# PowerBoard.net
KiCad netlist of a schematic drawn in Altium Designer
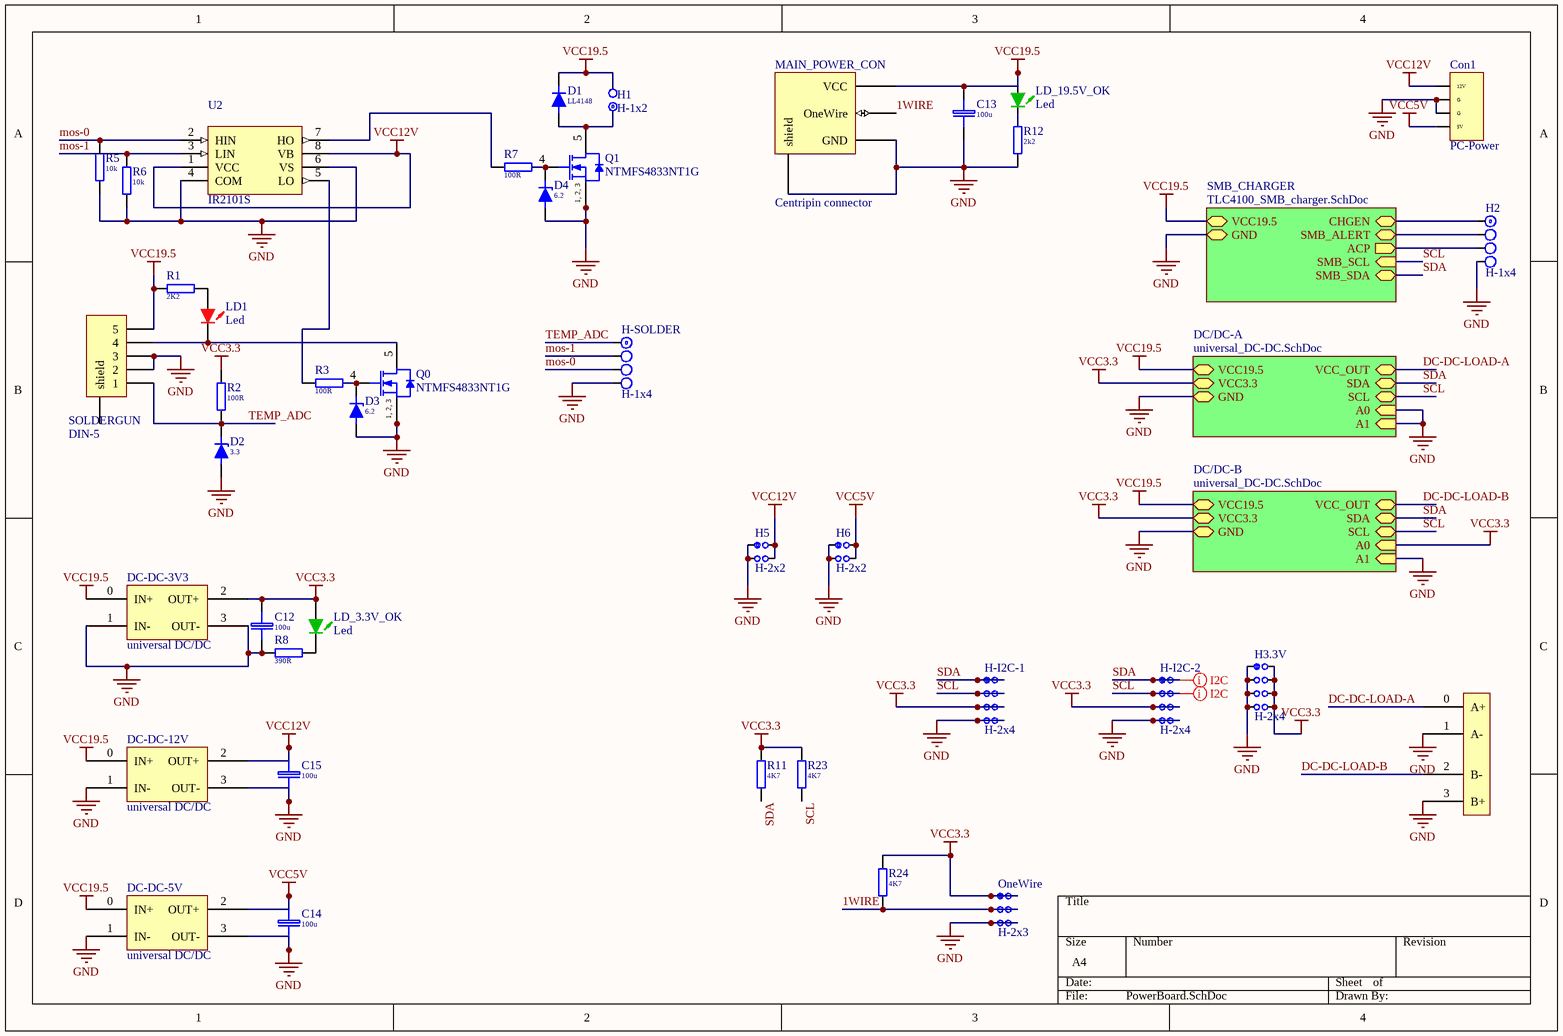
[diagram p0: PowerBoard.SchDoc]

(export (version "E")
  (design (tool "Eeschema 10.0.6"))
  (components
    (comp (ref "C12")
      (value "100u")
      (footprint "EL SMD Case G D10x10.3 h10.2(1010)")
      (description "EL 35V SMD Case G D10x10.3h10.5")
      (libsource (lib "SMD-RCL") (part "EL 100u/35V"))
    )
    (comp (ref "C13")
      (value "100u")
      (footprint "EL SMD Case G D10x10.3 h10.2(1010)")
      (description "EL 35V SMD Case G D10x10.3h10.5")
      (libsource (lib "SMD-RCL") (part "EL 100u/35V"))
    )
    (comp (ref "C14")
      (value "100u")
      (footprint "EL SMD Case G D10x10.3 h10.2(1010)")
      (description "EL 35V SMD Case G D10x10.3h10.5")
      (libsource (lib "SMD-RCL") (part "EL 100u/35V"))
    )
    (comp (ref "C15")
      (value "100u")
      (footprint "EL SMD Case G D10x10.3 h10.2(1010)")
      (description "EL 35V SMD Case G D10x10.3h10.5")
      (libsource (lib "SMD-RCL") (part "EL 100u/35V"))
    )
    (comp (ref "Con1")
      (value "PC-Power")
      (footprint "PC-Power 4x5.08")
      (description "PC-Power 4x5.08")
      (libsource (lib "Connektor") (part "PC-Power 4x5.08"))
    )
    (comp (ref "CON_DC_DC")
      (value "Speaker terminal 4P")
      (footprint "Speaker termina 4x DPS")
      (libsource (lib "Altium_okruh_miscLib") (part "Speaker terminal 4P"))
    )
    (comp (ref "D1")
      (value "LL4148")
      (footprint "Micro-Melf")
      (description "SMD Micro-Melf 75V 0.3A")
      (libsource (lib "Diodes") (part "MCL4148"))
    )
    (comp (ref "D2")
      (value "3.3")
      (footprint "SOD323")
      (description "3.3V 0.2W")
      (libsource (lib "Diodes") (part "ZD3.3"))
    )
    (comp (ref "D3")
      (value "6.2")
      (footprint "SOD323")
      (description "6.2V 0.2W")
      (libsource (lib "Diodes") (part "ZD6.2"))
    )
    (comp (ref "D4")
      (value "6.2")
      (footprint "SOD323")
      (description "6.2V 0.2W")
      (libsource (lib "Diodes") (part "ZD6.2"))
    )
    (comp (ref "DC-DC-3V3")
      (value "universal DC/DC")
      (footprint "MP1584EN dc/dc 3A vertical")
      (libsource (lib "Altium_okruh_miscLib") (part "universal DC/DC"))
    )
    (comp (ref "DC-DC-5V")
      (value "universal DC/DC")
      (footprint "MP1584EN dc/dc 3A vertical")
      (libsource (lib "Altium_okruh_miscLib") (part "universal DC/DC"))
    )
    (comp (ref "DC-DC-12V")
      (value "universal DC/DC")
      (footprint "MP1584EN dc/dc 3A vertical")
      (libsource (lib "Altium_okruh_miscLib") (part "universal DC/DC"))
    )
    (comp (ref "H-I2C-1") (value "H-2x4") (footprint "J2x4") (libsource (lib "Connektor") (part "H-2x4")))
    (comp (ref "H-I2C-2") (value "H-2x4") (footprint "J2x4") (libsource (lib "Connektor") (part "H-2x4")))
    (comp (ref "H-SOLDER") (value "H-1x4") (footprint "J1x4") (libsource (lib "Connektor") (part "H-1x4")))
    (comp (ref "H1") (value "H-1x2") (footprint "J1x2") (libsource (lib "Connektor") (part "H-1x2")))
    (comp (ref "H2") (value "H-1x4") (footprint "J1x4") (libsource (lib "Connektor") (part "H-1x4")))
    (comp (ref "H3.3V") (value "H-2x4") (footprint "J2x4") (libsource (lib "Connektor") (part "H-2x4")))
    (comp (ref "H5") (value "H-2x2") (footprint "J2x2") (libsource (lib "Connektor") (part "H-2x2")))
    (comp (ref "H6") (value "H-2x2") (footprint "J2x2") (libsource (lib "Connektor") (part "H-2x2")))
    (comp (ref "LD1")
      (value "Led")
      (footprint "Led 0805-Red")
      (description "Red  627nm 12mcd")
      (libsource (lib "Ind LED-LCD") (part "Led 0805 KP-2012EC"))
    )
    (comp (ref "LD_3.3V_OK")
      (value "Led")
      (footprint "Led 0805-Green")
      (description "Green 565nm 15mcd")
      (libsource (lib "Ind LED-LCD") (part "Led 0805 KP-2012SGC"))
    )
    (comp (ref "LD_19.5V_OK")
      (value "Led")
      (footprint "Led 0805-Green")
      (description "Green 565nm 15mcd")
      (libsource (lib "Ind LED-LCD") (part "Led 0805 KP-2012SGC"))
    )
    (comp (ref "MAIN_POWER_CON")
      (value "Centripin connector")
      (footprint "Dell_centripin")
      (libsource (lib "Altium_okruh_miscLib") (part "Centripin connector"))
    )
    (comp (ref "OneWire") (value "H-2x3") (footprint "J2x3") (libsource (lib "Connektor") (part "H-2x3")))
    (comp (ref "Q0")
      (value "NTMFS4833NT1G")
      (footprint "ONSC-DFN-5-488AA_V")
      (description "Power MOSFET, 30 V, 191 A, Single N-Channel, 5-Pin DFN, Pb-Free, Tape and Reel")
      (fields (field (name "MANUFACTURER") "On Semiconductor"))
      (libsource (lib "ON Semi MOSFETs") (part "NTMFS4833NT1G"))
    )
    (comp (ref "Q1")
      (value "NTMFS4833NT1G")
      (footprint "ONSC-DFN-5-488AA_V")
      (description "Power MOSFET, 30 V, 191 A, Single N-Channel, 5-Pin DFN, Pb-Free, Tape and Reel")
      (fields (field (name "MANUFACTURER") "On Semiconductor"))
      (libsource (lib "ON Semi MOSFETs") (part "NTMFS4833NT1G"))
    )
    (comp (ref "R1")
      (value "2K2")
      (footprint "R0805")
      (description "SMD 0805 0.1W 5% 150V")
      (libsource (lib "SMD-RCL") (part "R-0805"))
    )
    (comp (ref "R2")
      (value "100R")
      (footprint "R0805")
      (description "SMD 0805 0.1W 5% 150V")
      (libsource (lib "SMD-RCL") (part "R-0805"))
    )
    (comp (ref "R3")
      (value "100R")
      (footprint "R0805")
      (description "SMD 0805 0.1W 5% 150V")
      (libsource (lib "SMD-RCL") (part "R-0805"))
    )
    (comp (ref "R5")
      (value "10k")
      (footprint "R0805")
      (description "SMD 0805 0.1W 5% 150V")
      (libsource (lib "SMD-RCL") (part "R-0805"))
    )
    (comp (ref "R6")
      (value "10k")
      (footprint "R0805")
      (description "SMD 0805 0.1W 5% 150V")
      (libsource (lib "SMD-RCL") (part "R-0805"))
    )
    (comp (ref "R7")
      (value "100R")
      (footprint "R0805")
      (description "SMD 0805 0.1W 5% 150V")
      (libsource (lib "SMD-RCL") (part "R-0805"))
    )
    (comp (ref "R8")
      (value "390R")
      (footprint "R0805")
      (description "SMD 0805 0.1W 5% 150V")
      (libsource (lib "SMD-RCL") (part "R-0805"))
    )
    (comp (ref "R11")
      (value "4K7")
      (footprint "R0805")
      (description "SMD 0805 0.1W 5% 150V")
      (libsource (lib "SMD-RCL") (part "R-0805"))
    )
    (comp (ref "R12")
      (value "2k2")
      (footprint "R0805")
      (description "SMD 0805 0.1W 5% 150V")
      (libsource (lib "SMD-RCL") (part "R-0805"))
    )
    (comp (ref "R23")
      (value "4K7")
      (footprint "R0805")
      (description "SMD 0805 0.1W 5% 150V")
      (libsource (lib "SMD-RCL") (part "R-0805"))
    )
    (comp (ref "R24")
      (value "4K7")
      (footprint "R0805")
      (description "SMD 0805 0.1W 5% 150V")
      (libsource (lib "SMD-RCL") (part "R-0805"))
    )
    (comp (ref "SOLDERGUN")
      (value "DIN-5")
      (footprint "DIN-5")
      (libsource (lib "Altium_okruh_miscLib") (part "DIN-5"))
    )
    (comp (ref "U2")
      (value "IR2101S")
      (footprint "SO-8_L")
      (description "High and Low Side Driver")
      (fields (field (name "PUBLISHER") "Altium Limited"))
      (libsource (lib "IR Interface Bridge Driver") (part "IR2101S"))
    )
  )
  (nets
    (net (code "1") (name "/1WIRE") (class "Default")
      (node (ref "MAIN_POWER_CON") (pin "2") (pinfunction "OneWire_2") (pintype "bidirectional"))
      (node (ref "OneWire") (pin "3") (pinfunction "3_3") (pintype "passive"))
      (node (ref "OneWire") (pin "4") (pinfunction "4_4") (pintype "passive"))
      (node (ref "R24") (pin "1") (pinfunction "1_1") (pintype "passive"))
    )
    (net (code "2") (name "/ACP") (class "Default")
      (node (ref "H2") (pin "3") (pinfunction "3_3") (pintype "passive"))
    )
    (net (code "3") (name "/CHGEN") (class "Default")
      (node (ref "H2") (pin "1") (pinfunction "1_1") (pintype "passive"))
    )
    (net (code "4") (name "/DC-DC-LOAD-A") (class "Default")
      (node (ref "CON_DC_DC") (pin "0") (pinfunction "A+_0") (pintype "passive"))
    )
    (net (code "5") (name "/DC-DC-LOAD-B") (class "Default")
      (node (ref "CON_DC_DC") (pin "2") (pinfunction "B-_2") (pintype "passive"))
    )
    (net (code "6") (name "/SCL") (class "Default")
      (node (ref "H-I2C-1") (pin "3") (pinfunction "3_3") (pintype "passive"))
      (node (ref "H-I2C-1") (pin "4") (pinfunction "4_4") (pintype "passive"))
      (node (ref "H-I2C-2") (pin "3") (pinfunction "3_3") (pintype "passive"))
      (node (ref "H-I2C-2") (pin "4") (pinfunction "4_4") (pintype "passive"))
      (node (ref "R23") (pin "1") (pinfunction "1_1") (pintype "passive"))
    )
    (net (code "7") (name "/SDA") (class "Default")
      (node (ref "H-I2C-1") (pin "1") (pinfunction "1_1") (pintype "passive"))
      (node (ref "H-I2C-1") (pin "2") (pinfunction "2_2") (pintype "passive"))
      (node (ref "H-I2C-2") (pin "1") (pinfunction "1_1") (pintype "passive"))
      (node (ref "H-I2C-2") (pin "2") (pinfunction "2_2") (pintype "passive"))
      (node (ref "R11") (pin "1") (pinfunction "1_1") (pintype "passive"))
    )
    (net (code "8") (name "/SMB_ALERT") (class "Default")
      (node (ref "H2") (pin "2") (pinfunction "2_2") (pintype "passive"))
    )
    (net (code "9") (name "/TEMP_ADC") (class "Default")
      (node (ref "D2") (pin "2") (pinfunction "C_2") (pintype "passive"))
      (node (ref "H-SOLDER") (pin "1") (pinfunction "1_1") (pintype "passive"))
      (node (ref "R2") (pin "1") (pinfunction "1_1") (pintype "passive"))
      (node (ref "SOLDERGUN") (pin "1") (pinfunction "1_1") (pintype "passive"))
    )
    (net (code "10") (name "/mos-0") (class "Default")
      (node (ref "H-SOLDER") (pin "3") (pinfunction "3_3") (pintype "passive"))
      (node (ref "R5") (pin "2") (pinfunction "2_2") (pintype "passive"))
      (node (ref "U2") (pin "2") (pinfunction "HIN_2") (pintype "input"))
    )
    (net (code "11") (name "/mos-1") (class "Default")
      (node (ref "H-SOLDER") (pin "2") (pinfunction "2_2") (pintype "passive"))
      (node (ref "R6") (pin "2") (pinfunction "2_2") (pintype "passive"))
      (node (ref "U2") (pin "3") (pinfunction "LIN_3") (pintype "input"))
    )
    (net (code "12") (name "GND") (class "Default")
      (node (ref "C12") (pin "2") (pinfunction "-_2") (pintype "passive"))
      (node (ref "C13") (pin "2") (pinfunction "-_2") (pintype "passive"))
      (node (ref "C14") (pin "2") (pinfunction "-_2") (pintype "passive"))
      (node (ref "C15") (pin "2") (pinfunction "-_2") (pintype "passive"))
      (node (ref "CON_DC_DC") (pin "1") (pinfunction "A-_1") (pintype "passive"))
      (node (ref "CON_DC_DC") (pin "3") (pinfunction "B+_3") (pintype "passive"))
      (node (ref "Con1") (pin "2") (pinfunction "G_2") (pintype "passive"))
      (node (ref "Con1") (pin "3") (pinfunction "G_3") (pintype "passive"))
      (node (ref "D2") (pin "1") (pinfunction "A_1") (pintype "passive"))
      (node (ref "D3") (pin "1") (pinfunction "A_1") (pintype "passive"))
      (node (ref "D4") (pin "1") (pinfunction "A_1") (pintype "passive"))
      (node (ref "DC-DC-12V") (pin "1") (pinfunction "IN-_1") (pintype "power_in"))
      (node (ref "DC-DC-12V") (pin "3") (pinfunction "OUT-_3") (pintype "power_in"))
      (node (ref "DC-DC-3V3") (pin "1") (pinfunction "IN-_1") (pintype "power_in"))
      (node (ref "DC-DC-3V3") (pin "3") (pinfunction "OUT-_3") (pintype "power_in"))
      (node (ref "DC-DC-5V") (pin "1") (pinfunction "IN-_1") (pintype "power_in"))
      (node (ref "DC-DC-5V") (pin "3") (pinfunction "OUT-_3") (pintype "power_in"))
      (node (ref "H-I2C-1") (pin "7") (pinfunction "7_7") (pintype "passive"))
      (node (ref "H-I2C-1") (pin "8") (pinfunction "8_8") (pintype "passive"))
      (node (ref "H-I2C-2") (pin "7") (pinfunction "7_7") (pintype "passive"))
      (node (ref "H-I2C-2") (pin "8") (pinfunction "8_8") (pintype "passive"))
      (node (ref "H-SOLDER") (pin "4") (pinfunction "4_4") (pintype "passive"))
      (node (ref "H2") (pin "4") (pinfunction "4_4") (pintype "passive"))
      (node (ref "H3.3V") (pin "1") (pinfunction "1_1") (pintype "passive"))
      (node (ref "H3.3V") (pin "3") (pinfunction "3_3") (pintype "passive"))
      (node (ref "H3.3V") (pin "5") (pinfunction "5_5") (pintype "passive"))
      (node (ref "H3.3V") (pin "7") (pinfunction "7_7") (pintype "passive"))
      (node (ref "H5") (pin "1") (pinfunction "1_1") (pintype "passive"))
      (node (ref "H5") (pin "3") (pinfunction "3_3") (pintype "passive"))
      (node (ref "H6") (pin "1") (pinfunction "1_1") (pintype "passive"))
      (node (ref "H6") (pin "3") (pinfunction "3_3") (pintype "passive"))
      (node (ref "MAIN_POWER_CON") (pin "0") (pinfunction "shield_0") (pintype "passive"))
      (node (ref "MAIN_POWER_CON") (pin "1") (pinfunction "GND_1") (pintype "passive"))
      (node (ref "OneWire") (pin "5") (pinfunction "5_5") (pintype "passive"))
      (node (ref "OneWire") (pin "6") (pinfunction "6_6") (pintype "passive"))
      (node (ref "Q0") (pin "1") (pinfunction "S_1") (pintype "passive"))
      (node (ref "Q0") (pin "2") (pinfunction "S_2") (pintype "passive"))
      (node (ref "Q0") (pin "3") (pinfunction "S_3") (pintype "passive"))
      (node (ref "Q1") (pin "1") (pinfunction "S_1") (pintype "passive"))
      (node (ref "Q1") (pin "2") (pinfunction "S_2") (pintype "passive"))
      (node (ref "Q1") (pin "3") (pinfunction "S_3") (pintype "passive"))
      (node (ref "R12") (pin "2") (pinfunction "2_2") (pintype "passive"))
      (node (ref "R5") (pin "1") (pinfunction "1_1") (pintype "passive"))
      (node (ref "R6") (pin "1") (pinfunction "1_1") (pintype "passive"))
      (node (ref "R8") (pin "2") (pinfunction "2_2") (pintype "passive"))
      (node (ref "SOLDERGUN") (pin "2") (pinfunction "2_2") (pintype "passive"))
      (node (ref "SOLDERGUN") (pin "3") (pinfunction "3_3") (pintype "passive"))
      (node (ref "U2") (pin "4") (pinfunction "COM_4") (pintype "power_in"))
      (node (ref "U2") (pin "6") (pinfunction "VS_6") (pintype "power_in"))
    )
    (net (code "13") (name "Net-(D1-A)") (class "Default")
      (node (ref "D1") (pin "1") (pinfunction "A_1") (pintype "passive"))
      (node (ref "H1") (pin "1") (pinfunction "1_1") (pintype "passive"))
      (node (ref "Q1") (pin "5") (pinfunction "D_5") (pintype "passive"))
    )
    (net (code "14") (name "Net-(D3-C)") (class "Default")
      (node (ref "D3") (pin "2") (pinfunction "C_2") (pintype "passive"))
      (node (ref "Q0") (pin "4") (pinfunction "G_4") (pintype "passive"))
      (node (ref "R3") (pin "1") (pinfunction "1_1") (pintype "passive"))
    )
    (net (code "15") (name "Net-(D4-C)") (class "Default")
      (node (ref "D4") (pin "2") (pinfunction "C_2") (pintype "passive"))
      (node (ref "Q1") (pin "4") (pinfunction "G_4") (pintype "passive"))
      (node (ref "R7") (pin "1") (pinfunction "1_1") (pintype "passive"))
    )
    (net (code "16") (name "Net-(LD1-A)") (class "Default")
      (node (ref "LD1") (pin "1") (pinfunction "A_1") (pintype "passive"))
      (node (ref "R1") (pin "1") (pinfunction "1_1") (pintype "passive"))
    )
    (net (code "17") (name "Net-(LD1-K)") (class "Default")
      (node (ref "LD1") (pin "2") (pinfunction "K_2") (pintype "passive"))
      (node (ref "Q0") (pin "5") (pinfunction "D_5") (pintype "passive"))
      (node (ref "SOLDERGUN") (pin "4") (pinfunction "4_4") (pintype "passive"))
    )
    (net (code "18") (name "Net-(LD_3.3V_OK-K)") (class "Default")
      (node (ref "LD_3.3V_OK") (pin "2") (pinfunction "K_2") (pintype "passive"))
      (node (ref "R8") (pin "1") (pinfunction "1_1") (pintype "passive"))
    )
    (net (code "19") (name "Net-(LD_19.5V_OK-K)") (class "Default")
      (node (ref "LD_19.5V_OK") (pin "2") (pinfunction "K_2") (pintype "passive"))
      (node (ref "R12") (pin "1") (pinfunction "1_1") (pintype "passive"))
    )
    (net (code "20") (name "Net-(U2-HO)") (class "Default")
      (node (ref "R7") (pin "2") (pinfunction "2_2") (pintype "passive"))
      (node (ref "U2") (pin "7") (pinfunction "HO_7") (pintype "output"))
    )
    (net (code "21") (name "Net-(U2-LO)") (class "Default")
      (node (ref "R3") (pin "2") (pinfunction "2_2") (pintype "passive"))
      (node (ref "U2") (pin "5") (pinfunction "LO_5") (pintype "output"))
    )
    (net (code "22") (name "VCC3.3") (class "Default")
      (node (ref "C12") (pin "1") (pinfunction "+_1") (pintype "passive"))
      (node (ref "DC-DC-3V3") (pin "2") (pinfunction "OUT+_2") (pintype "power_in"))
      (node (ref "H-I2C-1") (pin "5") (pinfunction "5_5") (pintype "passive"))
      (node (ref "H-I2C-1") (pin "6") (pinfunction "6_6") (pintype "passive"))
      (node (ref "H-I2C-2") (pin "5") (pinfunction "5_5") (pintype "passive"))
      (node (ref "H-I2C-2") (pin "6") (pinfunction "6_6") (pintype "passive"))
      (node (ref "H3.3V") (pin "2") (pinfunction "2_2") (pintype "passive"))
      (node (ref "H3.3V") (pin "4") (pinfunction "4_4") (pintype "passive"))
      (node (ref "H3.3V") (pin "6") (pinfunction "6_6") (pintype "passive"))
      (node (ref "H3.3V") (pin "8") (pinfunction "8_8") (pintype "passive"))
      (node (ref "LD_3.3V_OK") (pin "1") (pinfunction "A_1") (pintype "passive"))
      (node (ref "OneWire") (pin "1") (pinfunction "1_1") (pintype "passive"))
      (node (ref "OneWire") (pin "2") (pinfunction "2_2") (pintype "passive"))
      (node (ref "R11") (pin "2") (pinfunction "2_2") (pintype "passive"))
      (node (ref "R2") (pin "2") (pinfunction "2_2") (pintype "passive"))
      (node (ref "R23") (pin "2") (pinfunction "2_2") (pintype "passive"))
      (node (ref "R24") (pin "2") (pinfunction "2_2") (pintype "passive"))
    )
    (net (code "23") (name "VCC5V") (class "Default")
      (node (ref "C14") (pin "1") (pinfunction "+_1") (pintype "passive"))
      (node (ref "Con1") (pin "1") (pinfunction "5V_1") (pintype "passive"))
      (node (ref "DC-DC-5V") (pin "2") (pinfunction "OUT+_2") (pintype "power_in"))
      (node (ref "H6") (pin "2") (pinfunction "2_2") (pintype "passive"))
      (node (ref "H6") (pin "4") (pinfunction "4_4") (pintype "passive"))
    )
    (net (code "24") (name "VCC12V") (class "Default")
      (node (ref "C15") (pin "1") (pinfunction "+_1") (pintype "passive"))
      (node (ref "Con1") (pin "4") (pinfunction "12V_4") (pintype "passive"))
      (node (ref "DC-DC-12V") (pin "2") (pinfunction "OUT+_2") (pintype "power_in"))
      (node (ref "H5") (pin "2") (pinfunction "2_2") (pintype "passive"))
      (node (ref "H5") (pin "4") (pinfunction "4_4") (pintype "passive"))
      (node (ref "U2") (pin "1") (pinfunction "VCC_1") (pintype "power_in"))
      (node (ref "U2") (pin "8") (pinfunction "VB_8") (pintype "power_in"))
    )
    (net (code "25") (name "VCC19.5") (class "Default")
      (node (ref "C13") (pin "1") (pinfunction "+_1") (pintype "passive"))
      (node (ref "D1") (pin "2") (pinfunction "C_2") (pintype "passive"))
      (node (ref "DC-DC-12V") (pin "0") (pinfunction "IN+_0") (pintype "power_in"))
      (node (ref "DC-DC-3V3") (pin "0") (pinfunction "IN+_0") (pintype "power_in"))
      (node (ref "DC-DC-5V") (pin "0") (pinfunction "IN+_0") (pintype "power_in"))
      (node (ref "H1") (pin "2") (pinfunction "2_2") (pintype "passive"))
      (node (ref "LD_19.5V_OK") (pin "1") (pinfunction "A_1") (pintype "passive"))
      (node (ref "MAIN_POWER_CON") (pin "3") (pinfunction "VCC_3") (pintype "power_in"))
      (node (ref "R1") (pin "2") (pinfunction "2_2") (pintype "passive"))
      (node (ref "SOLDERGUN") (pin "5") (pinfunction "5_5") (pintype "passive"))
    )
    (net (code "26") (name "unconnected-(SOLDERGUN-shield-Pad0)") (class "Default")
      (node (ref "SOLDERGUN") (pin "0") (pinfunction "shield_0") (pintype "passive"))
    )
  )
)
